# Main_cicuit.net
KiCad netlist of a schematic drawn in Altium Designer
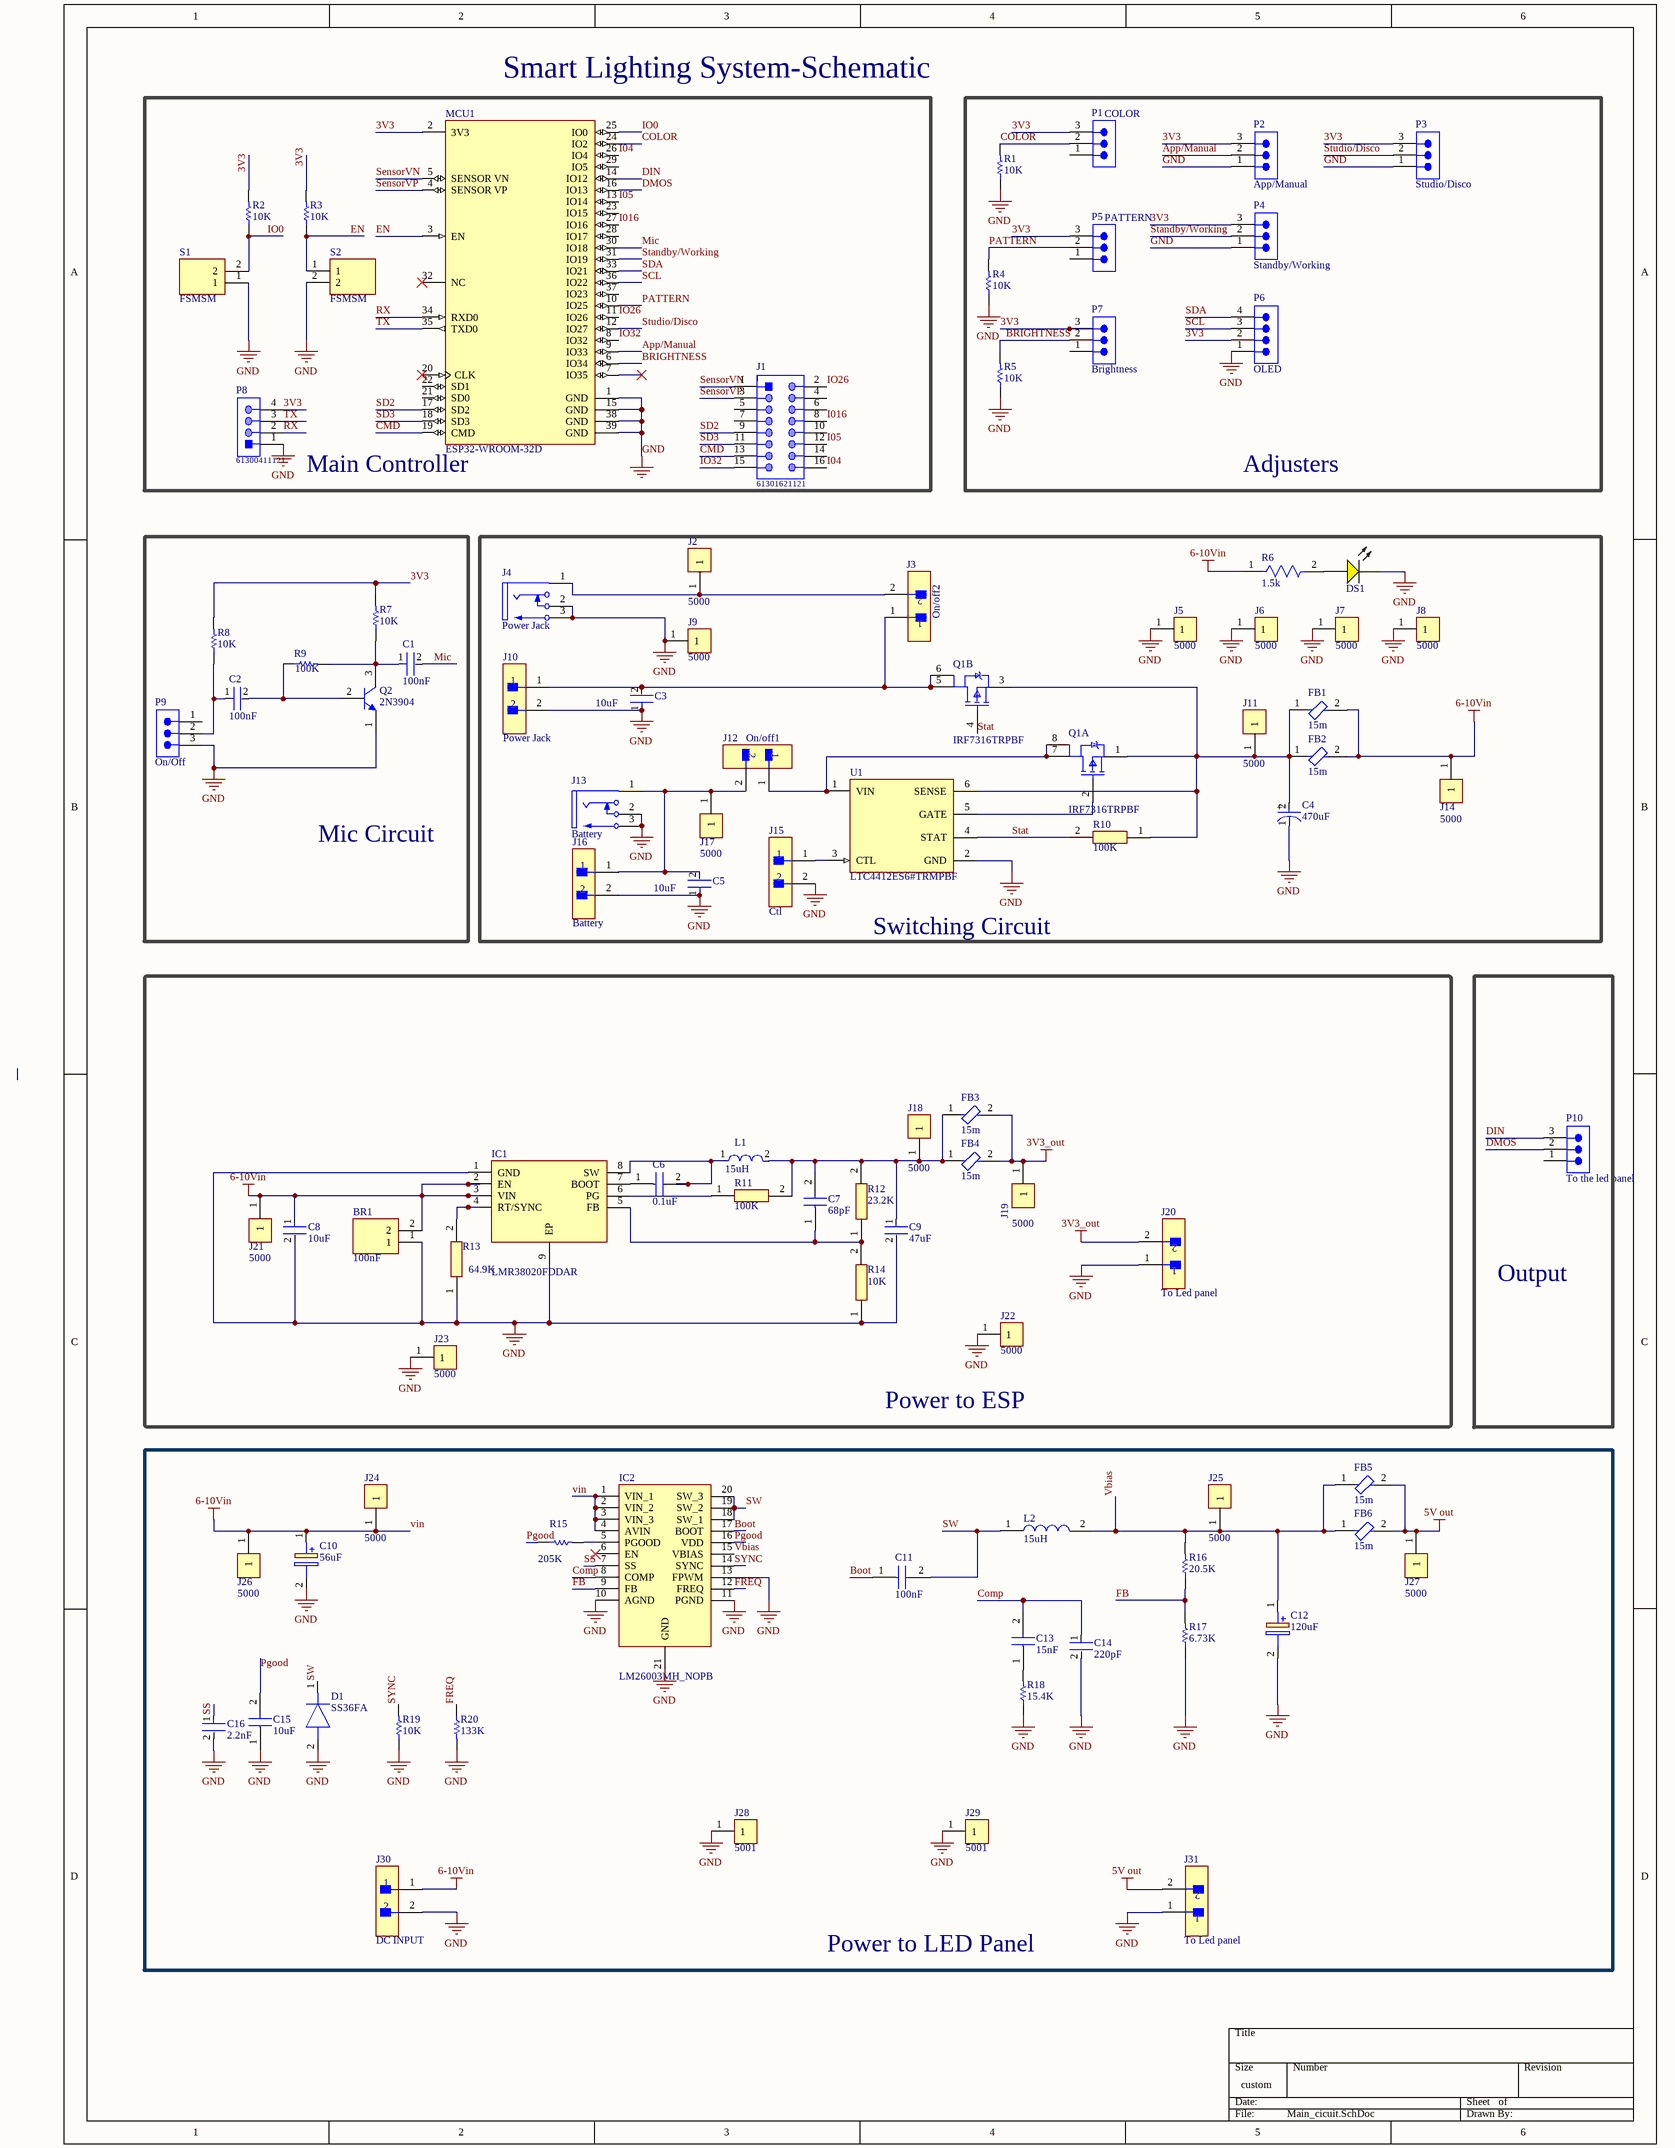
[diagram p0: Main_cicuit.SchDoc]

(export (version "E")
  (design (tool "Eeschema 10.0.6"))
  (components
    (comp (ref "BR1")
      (value "100nF")
      (footprint "SamacSys:CAPC3216X140N")
      (description "Bridge Rectifier")
      (fields
        (field (name "MANUFACTURER_PART_NUMBER") "C1206C104M4RECTU")
        (field (name "MOUSER PART NUMBER") "80-C1206C104M4RECTU")
      )
      (libsource (lib "*") (part "C1206C104M4RECTU"))
    )
    (comp (ref "C1")
      (value "100nF")
      (footprint "FP-CL31-IPC_C")
      (description "Cap Ceramic 100nF 100V X7R ±10% SMD 1206 +125°C Embossed T/R")
      (fields (field (name "VOLTAGE") "100V") (field (name "TOLERANCE") "10%"))
      (libsource (lib "Altium Content Vault") (part "b4654b650e69147ec39a6b967a45e02"))
    )
    (comp (ref "C2")
      (value "100nF")
      (footprint "FP-CL31-IPC_C")
      (description "Cap Ceramic 100nF 100V X7R ±10% SMD 1206 +125°C Embossed T/R")
      (fields (field (name "VOLTAGE") "100V") (field (name "TOLERANCE") "10%"))
      (libsource (lib "Altium Content Vault") (part "b4654b650e69147ec39a6b967a45e02"))
    )
    (comp (ref "C3")
      (value "10uF")
      (footprint "FP-CL21B106KOQNNNG-MFG")
      (description "CAP CER 10UF 16V X7R 0805")
      (fields (field (name "TOLERANCE") "10%") (field (name "MANUFACTURER PART NUMBER") "CL21B106KOQNNNG"))
      (libsource (lib "Altium Content Vault") (part "b4654b650e69147ec39a6b967a45e02"))
    )
    (comp (ref "C4")
      (value "470uF")
      (footprint "FP-FTF-MFG")
      (description "CAP ALUM 470UF 20% 25V SMD")
      (fields (field (name "VOLTAGE") "25V") (field (name "TOLERANCE") "20%"))
      (libsource (lib "Altium Content Vault") (part "a00bbbee19879c290e62620ae7e47b1"))
    )
    (comp (ref "C5")
      (value "10uF")
      (footprint "FP-CL21B106KOQNNNG-MFG")
      (description "CAP CER 10UF 16V X7R 0805")
      (fields (field (name "TOLERANCE") "10%") (field (name "MANUFACTURER PART NUMBER") "CL21B106KOQNNNG"))
      (libsource (lib "Altium Content Vault") (part "b4654b650e69147ec39a6b967a45e02"))
    )
    (comp (ref "C6")
      (value "0.1uF")
      (footprint "SamacSys:CAPC3216X200N")
      (description "Capacitor")
      (fields
        (field (name "MANUFACTURER_PART_NUMBER") "GCJ31CR72E104KXJ3L")
        (field (name "MOUSER PART NUMBER") "81-GCJ31CR72E104KX3L")
      )
      (libsource (lib "*") (part "GCJ31CR72E104KXJ3L"))
    )
    (comp (ref "C7")
      (value "68pF")
      (footprint "SamacSys:CAPC3216X90N")
      (description "Capacitor")
      (fields (field (name "MANUFACTURER_PART_NUMBER") "885012008022"))
      (libsource (lib "*") (part "885012008022"))
    )
    (comp (ref "C8")
      (value "10uF")
      (footprint "FP-GRM31C-0_2-e0_3_0_8-MFG")
      (description "Chip Multilayer Ceramic Capacitors for General Purpose, 1206, 10uF, X7R, 15%, 10%, 25V")
      (fields (field (name "TOLERANCE") "10%") (field (name "VOLTAGE") "25V"))
      (libsource (lib "Altium Content Vault") (part "02cd4be3c70576c341d710602a673aa"))
    )
    (comp (ref "C9")
      (value "47uF")
      (footprint "FP-1206-L_3_2_0_3-W_1_6_0-MFG")
      (description "None")
      (fields (field (name "TOLERANCE") "20%"))
      (libsource (lib "Altium Content Vault") (part "11868f565c42a9108669ba33697ecf6"))
    )
    (comp (ref "C10")
      (value "56uF")
      (footprint "SamacSys:EEHZA1E101XP")
      (description "Capacitor Polarised")
      (fields
        (field (name "MANUFACTURER_PART_NUMBER") "EEH-ZC1E560P")
        (field (name "MOUSER PART NUMBER") "667-EEH-ZC1E560P")
      )
      (libsource (lib "*") (part "EEH-ZC1E560P"))
    )
    (comp (ref "C11")
      (value "100nF")
      (footprint "SamacSys:CAPC2013X94N")
      (description "Capacitor")
      (fields
        (field (name "MANUFACTURER_PART_NUMBER") "08053C104JAZ2A")
        (field (name "MOUSER PART NUMBER") "581-08053C104JAZ2A")
      )
      (libsource (lib "*") (part "08053C104JAZ2A"))
    )
    (comp (ref "C12")
      (value "120uF")
      (footprint "SamacSys:10SVPC120M")
      (description "Capacitor Polarised")
      (fields
        (field (name "MANUFACTURER_PART_NUMBER") "10SVPC120M")
        (field (name "MOUSER PART NUMBER") "667-10SVPC120M")
      )
      (libsource (lib "*") (part "10SVPC120M"))
    )
    (comp (ref "C13")
      (value "15nF")
      (footprint "SamacSys:C2012_Commercial")
      (description "Capacitor")
      (fields
        (field (name "MANUFACTURER_PART_NUMBER") "C2012C0G1H153J085AA")
        (field (name "MOUSER PART NUMBER") "810-C2012C0G1H153J")
      )
      (libsource (lib "*") (part "C2012C0G1H153J085AA"))
    )
    (comp (ref "C14")
      (value "220pF")
      (footprint "FP-CL21-IPC_B")
      (description "CL21 Series 0805 220pF 50V ±5% Tolerance C0G Multilayer Ceramic Chip Capacitor")
      (fields (field (name "TOLERANCE") "5%") (field (name "VOLTAGE") "50V"))
      (libsource (lib "Altium Content Vault") (part "b4654b650e69147ec39a6b967a45e02"))
    )
    (comp (ref "C15")
      (value "10uF")
      (footprint "SamacSys:CAPC3216X170N")
      (description "Capacitor")
      (fields
        (field (name "MANUFACTURER_PART_NUMBER") "VJ1206G106KXYTW1BC")
        (field (name "MOUSER PART NUMBER") "77-VJ1206G106KXYTBC")
      )
      (libsource (lib "*") (part "VJ1206G106KXYTW1BC"))
    )
    (comp (ref "C16")
      (value "2.2nF")
      (footprint "FP-CL21-IPC_C")
      (description "CL21 Series 0805 2.2nF 50V ±5% Tolerance C0G Multilayer Ceramic Chip Capacitor")
      (fields (field (name "TOLERANCE") "5%") (field (name "VOLTAGE") "50V"))
      (libsource (lib "Altium Content Vault") (part "b4654b650e69147ec39a6b967a45e02"))
    )
    (comp (ref "D1")
      (value "SS36FA")
      (footprint "SamacSys:SODFL3618X143N")
      (description "Diode")
      (fields (field (name "MOUSER PART NUMBER") "512-SS36FA"))
      (libsource (lib "*") (part "SS36FA"))
    )
    (comp (ref "DS1")
      (value "SML-LX1206YC-TR")
      (footprint "LUMX-SML-LX1206YC-TR_V")
      (description "Yellow LED, Water Clear Len, 585 nm, 2.1 V, -40 to 85 degC, 2-Pin SMD, RoHS, Tape and Reel")
      (fields (field (name "MANUFACTURER") "Lumex"))
      (libsource (lib "Altium Content Vault") (part "LED-YELLOW-AK-2"))
    )
    (comp (ref "FB1")
      (value "15m")
      (footprint "FP-BLM21-0_2-t0_85-e0_5-d-IPC_B")
      (description "Chip Ferrite Bead, 0805, 30Ω @ 100MHz, 0.014Ω, , 4A")
      (fields (field (name "TOLERANCE") "25%"))
      (libsource (lib "Altium Content Vault") (part "5f30dd21d616792df468990f7003faa"))
    )
    (comp (ref "FB2")
      (value "15m")
      (footprint "FP-BLM21-0_2-t0_85-e0_5-d-IPC_B")
      (description "Chip Ferrite Bead, 0805, 30Ω @ 100MHz, 0.014Ω, , 4A")
      (fields (field (name "TOLERANCE") "25%"))
      (libsource (lib "Altium Content Vault") (part "5f30dd21d616792df468990f7003faa"))
    )
    (comp (ref "FB3")
      (value "15m")
      (footprint "FP-BLM21-0_2-t0_85-e0_5-d-IPC_B")
      (description "Chip Ferrite Bead, 0805, 30Ω @ 100MHz, 0.014Ω, , 4A")
      (fields (field (name "TOLERANCE") "25%"))
      (libsource (lib "Altium Content Vault") (part "5f30dd21d616792df468990f7003faa"))
    )
    (comp (ref "FB4")
      (value "15m")
      (footprint "FP-BLM21-0_2-t0_85-e0_5-d-IPC_B")
      (description "Chip Ferrite Bead, 0805, 30Ω @ 100MHz, 0.014Ω, , 4A")
      (fields (field (name "TOLERANCE") "25%"))
      (libsource (lib "Altium Content Vault") (part "5f30dd21d616792df468990f7003faa"))
    )
    (comp (ref "FB5")
      (value "15m")
      (footprint "FP-BLM21-0_2-t0_85-e0_5-d-IPC_B")
      (description "Chip Ferrite Bead, 0805, 30Ω @ 100MHz, 0.014Ω, , 4A")
      (fields (field (name "TOLERANCE") "25%"))
      (libsource (lib "Altium Content Vault") (part "5f30dd21d616792df468990f7003faa"))
    )
    (comp (ref "FB6")
      (value "15m")
      (footprint "FP-BLM21-0_2-t0_85-e0_5-d-IPC_B")
      (description "Chip Ferrite Bead, 0805, 30Ω @ 100MHz, 0.014Ω, , 4A")
      (fields (field (name "TOLERANCE") "25%"))
      (libsource (lib "Altium Content Vault") (part "5f30dd21d616792df468990f7003faa"))
    )
    (comp (ref "IC1")
      (value "LMR38020FDDAR")
      (footprint "SamacSys:SOIC127P600X170-9N")
      (description "Integrated Circuit")
      (fields (field (name "MOUSER PART NUMBER") "595-LMR38020FDDAR"))
      (libsource (lib "*") (part "LMR38020FDDAR"))
    )
    (comp (ref "IC2")
      (value "LM26003MH_NOPB")
      (footprint "SamacSys:SOP65P640X110-21N")
      (description "Integrated Circuit")
      (fields
        (field (name "MANUFACTURER_PART_NUMBER") "LM26003MH/NOPB")
        (field (name "MOUSER PART NUMBER") "926-LM26003MH/NOPB")
      )
      (libsource (lib "*") (part "LM26003MH_NOPB"))
    )
    (comp (ref "J1")
      (value "61301621121")
      (footprint "61301621121")
      (description "THT Vertical Pin Header WR-PHD, Pitch 2.54 mm, Dual Row, 16 pins")
      (fields (field (name "MANUFACTURER") "Wurth Elektronik") (field (name "PUBLISHER") "WurthElektronik"))
      (libsource (lib "Altium Content Vault") (part "WE-CN-2P-M-R16"))
    )
    (comp (ref "J2")
      (value "5000")
      (footprint "FP-5000-MFG")
      (description "PC TEST POINT MINIATURE RED")
      (libsource (lib "") (part "1e4615820a309e3ce90f9e6d957b7fa_1"))
    )
    (comp (ref "J3")
      (value "On/off2")
      (footprint "FP-61900211121-MFG")
      (description "CONN HEADER VERT 2POS 2.54MM")
      (libsource (lib "") (part "3bc925449376181038e59eaffc5286c_1"))
    )
    (comp (ref "J4")
      (value "Power Jack")
      (footprint "SWITCH-RAPC712X-3_V")
      (description "Power Jack, 5 A, 3-Pin THD, RoHS, Bulk")
      (fields (field (name "MANUFACTURER") "Switchcraft"))
      (libsource (lib "Altium Content Vault") (part "SWITCH-RAPC712X-3"))
    )
    (comp (ref "J5")
      (value "5000")
      (footprint "FP-5000-MFG")
      (description "PC TEST POINT MINIATURE RED")
      (libsource (lib "Altium Content Vault") (part "1e4615820a309e3ce90f9e6d957b7fa"))
    )
    (comp (ref "J6")
      (value "5000")
      (footprint "FP-5000-MFG")
      (description "PC TEST POINT MINIATURE RED")
      (libsource (lib "Altium Content Vault") (part "1e4615820a309e3ce90f9e6d957b7fa"))
    )
    (comp (ref "J7")
      (value "5000")
      (footprint "FP-5000-MFG")
      (description "PC TEST POINT MINIATURE RED")
      (libsource (lib "Altium Content Vault") (part "1e4615820a309e3ce90f9e6d957b7fa"))
    )
    (comp (ref "J8")
      (value "5000")
      (footprint "FP-5000-MFG")
      (description "PC TEST POINT MINIATURE RED")
      (libsource (lib "Altium Content Vault") (part "1e4615820a309e3ce90f9e6d957b7fa"))
    )
    (comp (ref "J9")
      (value "5000")
      (footprint "FP-5000-MFG")
      (description "PC TEST POINT MINIATURE RED")
      (libsource (lib "Altium Content Vault") (part "1e4615820a309e3ce90f9e6d957b7fa"))
    )
    (comp (ref "J10")
      (value "Power Jack")
      (footprint "FP-61900211121-MFG")
      (description "CONN HEADER VERT 2POS 2.54MM")
      (libsource (lib "Altium Content Vault") (part "3bc925449376181038e59eaffc5286c"))
    )
    (comp (ref "J11")
      (value "5000")
      (footprint "FP-5000-MFG")
      (description "PC TEST POINT MINIATURE RED")
      (libsource (lib "") (part "1e4615820a309e3ce90f9e6d957b7fa_1"))
    )
    (comp (ref "J12")
      (value "On/off1")
      (footprint "FP-61900211121-MFG")
      (description "CONN HEADER VERT 2POS 2.54MM")
      (libsource (lib "") (part "3bc925449376181038e59eaffc5286c_2"))
    )
    (comp (ref "J13")
      (value "Battery")
      (footprint "SWITCH-RAPC712X-3_V")
      (description "Power Jack, 5 A, 3-Pin THD, RoHS, Bulk")
      (fields (field (name "MANUFACTURER") "Switchcraft"))
      (libsource (lib "Altium Content Vault") (part "SWITCH-RAPC712X-3"))
    )
    (comp (ref "J14")
      (value "5000")
      (footprint "FP-5000-MFG")
      (description "PC TEST POINT MINIATURE RED")
      (libsource (lib "") (part "1e4615820a309e3ce90f9e6d957b7fa_2"))
    )
    (comp (ref "J15")
      (value "Ctl")
      (footprint "FP-61900211121-MFG")
      (description "CONN HEADER VERT 2POS 2.54MM")
      (libsource (lib "Altium Content Vault") (part "3bc925449376181038e59eaffc5286c"))
    )
    (comp (ref "J16")
      (value "Battery")
      (footprint "FP-61900211121-MFG")
      (description "CONN HEADER VERT 2POS 2.54MM")
      (libsource (lib "Altium Content Vault") (part "3bc925449376181038e59eaffc5286c"))
    )
    (comp (ref "J17")
      (value "5000")
      (footprint "FP-5000-MFG")
      (description "PC TEST POINT MINIATURE RED")
      (libsource (lib "") (part "1e4615820a309e3ce90f9e6d957b7fa_2"))
    )
    (comp (ref "J18")
      (value "5000")
      (footprint "FP-5000-MFG")
      (description "PC TEST POINT MINIATURE RED")
      (libsource (lib "") (part "1e4615820a309e3ce90f9e6d957b7fa_1"))
    )
    (comp (ref "J19")
      (value "5000")
      (footprint "FP-5000-MFG")
      (description "PC TEST POINT MINIATURE RED")
      (libsource (lib "") (part "1e4615820a309e3ce90f9e6d957b7fa_2"))
    )
    (comp (ref "J20")
      (value "To Led panel")
      (footprint "FP-61900211121-MFG")
      (description "CONN HEADER VERT 2POS 2.54MM")
      (libsource (lib "") (part "3bc925449376181038e59eaffc5286c_1"))
    )
    (comp (ref "J21")
      (value "5000")
      (footprint "FP-5000-MFG")
      (description "PC TEST POINT MINIATURE RED")
      (libsource (lib "") (part "1e4615820a309e3ce90f9e6d957b7fa_2"))
    )
    (comp (ref "J22")
      (value "5000")
      (footprint "FP-5000-MFG")
      (description "PC TEST POINT MINIATURE RED")
      (libsource (lib "Altium Content Vault") (part "1e4615820a309e3ce90f9e6d957b7fa"))
    )
    (comp (ref "J23")
      (value "5000")
      (footprint "FP-5000-MFG")
      (description "PC TEST POINT MINIATURE RED")
      (libsource (lib "Altium Content Vault") (part "1e4615820a309e3ce90f9e6d957b7fa"))
    )
    (comp (ref "J24")
      (value "5000")
      (footprint "FP-5000-MFG")
      (description "PC TEST POINT MINIATURE RED")
      (libsource (lib "") (part "1e4615820a309e3ce90f9e6d957b7fa_1"))
    )
    (comp (ref "J25")
      (value "5000")
      (footprint "FP-5000-MFG")
      (description "PC TEST POINT MINIATURE RED")
      (libsource (lib "") (part "1e4615820a309e3ce90f9e6d957b7fa_1"))
    )
    (comp (ref "J26")
      (value "5000")
      (footprint "FP-5000-MFG")
      (description "PC TEST POINT MINIATURE RED")
      (libsource (lib "") (part "1e4615820a309e3ce90f9e6d957b7fa_2"))
    )
    (comp (ref "J27")
      (value "5000")
      (footprint "FP-5000-MFG")
      (description "PC TEST POINT MINIATURE RED")
      (libsource (lib "") (part "1e4615820a309e3ce90f9e6d957b7fa_2"))
    )
    (comp (ref "J28")
      (value "5001")
      (footprint "FP-5001-MFG")
      (description "PC TEST POINT MINIATURE BLACK")
      (libsource (lib "Altium Content Vault") (part "1e4615820a309e3ce90f9e6d957b7fa"))
    )
    (comp (ref "J29")
      (value "5001")
      (footprint "FP-5001-MFG")
      (description "PC TEST POINT MINIATURE BLACK")
      (libsource (lib "Altium Content Vault") (part "1e4615820a309e3ce90f9e6d957b7fa"))
    )
    (comp (ref "J30")
      (value "DC INPUT")
      (footprint "FP-61900211121-MFG")
      (description "CONN HEADER VERT 2POS 2.54MM")
      (libsource (lib "Altium Content Vault") (part "3bc925449376181038e59eaffc5286c"))
    )
    (comp (ref "J31")
      (value "To Led panel")
      (footprint "FP-61900211121-MFG")
      (description "CONN HEADER VERT 2POS 2.54MM")
      (libsource (lib "") (part "3bc925449376181038e59eaffc5286c_1"))
    )
    (comp (ref "L1")
      (value "15uH")
      (footprint "FP-SRR1260-MFG")
      (description "FIXED IND 15UH 5A 27 MOHM SMD")
      (fields (field (name "TOLERANCE") "20%"))
      (libsource (lib "Altium Content Vault") (part "725321dda6339637d4d059423bc1c3c"))
    )
    (comp (ref "L2")
      (value "15uH")
      (footprint "SamacSys:INDPM7366X300N")
      (description "Inductor")
      (fields
        (field (name "MANUFACTURER_PART_NUMBER") "SRP7028A-150M")
        (field (name "MOUSER PART NUMBER") "652-SRP7028A-150M")
      )
      (libsource (lib "*") (part "SRP7028A-150M"))
    )
    (comp (ref "MCU1")
      (value "ESP32-WROOM-32D")
      (footprint "FP-ESP32-WROOM-32D-MFG")
      (description "WIFI MODULE 32MBITS SPI FLASH")
      (fields
        (field (name "OCTOPART") "https://octopart.com/esp32-wroom-32d-espressif+systems-91040050")
        (field (name "MANUFACTURER") "Espressif Systems")
      )
      (libsource (lib "Altium Content Vault") (part "a031a76f8c27026a7a7f4657ff233a3"))
    )
    (comp (ref "P1")
      (value "COLOR")
      (footprint "SMTC-TSW-103-07-X-S")
      (description "0.025\" SQ Post Header, Through-hole, Vertical, -55 to 125 degC, 2.54 mm Pitch, 3-Pin, Male, RoHS")
      (fields (field (name "MANUFACTURER") "Samtec") (field (name "PARTNUMBER") "TSW-103-07-F-S"))
      (libsource (lib "Altium Content Vault") (part "SMTC-TSW-103-X-X-S-X"))
    )
    (comp (ref "P2")
      (value "App/Manual")
      (footprint "SMTC-TSW-103-07-X-S")
      (description "0.025\" SQ Post Header, Through-hole, Vertical, -55 to 125 degC, 2.54 mm Pitch, 3-Pin, Male, RoHS")
      (fields (field (name "MANUFACTURER") "Samtec") (field (name "PARTNUMBER") "TSW-103-07-F-S"))
      (libsource (lib "Altium Content Vault") (part "SMTC-TSW-103-X-X-S-X"))
    )
    (comp (ref "P3")
      (value "Studio/Disco")
      (footprint "SMTC-TSW-103-07-X-S")
      (description "0.025\" SQ Post Header, Through-hole, Vertical, -55 to 125 degC, 2.54 mm Pitch, 3-Pin, Male, RoHS")
      (fields (field (name "MANUFACTURER") "Samtec") (field (name "PARTNUMBER") "TSW-103-07-F-S"))
      (libsource (lib "Altium Content Vault") (part "SMTC-TSW-103-X-X-S-X"))
    )
    (comp (ref "P4")
      (value "Standby/Working")
      (footprint "SMTC-TSW-103-07-X-S")
      (description "0.025\" SQ Post Header, Through-hole, Vertical, -55 to 125 degC, 2.54 mm Pitch, 3-Pin, Male, RoHS")
      (fields (field (name "MANUFACTURER") "Samtec") (field (name "PARTNUMBER") "TSW-103-07-F-S"))
      (libsource (lib "Altium Content Vault") (part "SMTC-TSW-103-X-X-S-X"))
    )
    (comp (ref "P5")
      (value "PATTERN")
      (footprint "SMTC-TSW-103-07-X-S")
      (description "0.025\" SQ Post Header, Through-hole, Vertical, -55 to 125 degC, 2.54 mm Pitch, 3-Pin, Male, RoHS")
      (fields (field (name "MANUFACTURER") "Samtec") (field (name "PARTNUMBER") "TSW-103-07-F-S"))
      (libsource (lib "Altium Content Vault") (part "SMTC-TSW-103-X-X-S-X"))
    )
    (comp (ref "P6")
      (value "OLED")
      (footprint "SMTC-TSW-104-08-X-S")
      (description "0.025\" SQ Post Header, Through-hole, Vertical, -55 to 125 degC, 2.54 mm Pitch, 4-Pin, Male, RoHS")
      (fields (field (name "MANUFACTURER") "Samtec") (field (name "PARTNUMBER") "TSW-104-08-G-S"))
      (libsource (lib "Altium Content Vault") (part "SMTC-TSW-104-08-X-S"))
    )
    (comp (ref "P7")
      (value "Brightness")
      (footprint "SMTC-TSW-103-07-X-S")
      (description "0.025\" SQ Post Header, Through-hole, Vertical, -55 to 125 degC, 2.54 mm Pitch, 3-Pin, Male, RoHS")
      (fields (field (name "MANUFACTURER") "Samtec") (field (name "PARTNUMBER") "TSW-103-07-F-S"))
      (libsource (lib "Altium Content Vault") (part "SMTC-TSW-103-X-X-S-X"))
    )
    (comp (ref "P8")
      (value "61300411121")
      (footprint "61300411121")
      (description "THT Vertical Pin Header WR-PHD, Pitch 2.54 mm, Single Row, 4 pins")
      (fields (field (name "MANUFACTURER") "Wurth Elektronik") (field (name "PUBLISHER") "WurthElektronik"))
      (libsource (lib "Altium Content Vault") (part "WE-CN-1P-M-R4"))
    )
    (comp (ref "P9")
      (value "On/Off")
      (footprint "SMTC-TSW-103-07-X-S")
      (description "0.025\" SQ Post Header, Through-hole, Vertical, -55 to 125 degC, 2.54 mm Pitch, 3-Pin, Male, RoHS")
      (fields (field (name "MANUFACTURER") "Samtec") (field (name "PARTNUMBER") "TSW-103-07-F-S"))
      (libsource (lib "Altium Content Vault") (part "SMTC-TSW-103-X-X-S-X"))
    )
    (comp (ref "P10")
      (value "To the led panel")
      (footprint "SMTC-TSW-103-07-X-S")
      (description "0.025\" SQ Post Header, Through-hole, Vertical, -55 to 125 degC, 2.54 mm Pitch, 3-Pin, Male, RoHS")
      (fields (field (name "MANUFACTURER") "Samtec") (field (name "PARTNUMBER") "TSW-103-07-F-S"))
      (libsource (lib "Altium Content Vault") (part "SMTC-TSW-103-X-X-S-X"))
    )
    (comp (ref "Q1")
      (value "IRF7316TRPBF")
      (footprint "FP-PG-DSO-8-IPC_B")
      (description "MOSFET 2P-CH 30V 4.9A 8-SOIC")
      (libsource (lib "Altium Content Vault") (part "492061ec32f27a5842dd38c1d0dc3fb"))
    )
    (comp (ref "Q2")
      (value "2N3904")
      (footprint "ONSC-TO-92-3-29-11")
      (description "General Purpose Transistor, NPN Silicon, 200 mA, 60 V, -55 to 150 degC, 3-Pin TO-92, RoHS, Bulk")
      (fields (field (name "MANUFACTURER") "ONSemiconductor"))
      (libsource (lib "Altium Content Vault") (part "BJT-NPN-EBC-3"))
    )
    (comp (ref "R1")
      (value "10K")
      (footprint "RESC3116X65X40ML10T20")
      (description "Chip Resistor, 10 KOhm, +/- 1%, 0.25 W, -55 to 155 degC, 1206 (3216 Metric), RoHS, Tape and Reel")
      (fields (field (name "TOLERANCE") "1%") (field (name "MANUFACTURER") "Yageo"))
      (libsource (lib "Altium Content Vault") (part "RES-2"))
    )
    (comp (ref "R2")
      (value "10K")
      (footprint "RESC3116X65X40ML10T20")
      (description "Chip Resistor, 10 KOhm, +/- 1%, 0.25 W, -55 to 155 degC, 1206 (3216 Metric), RoHS, Tape and Reel")
      (fields (field (name "TOLERANCE") "1%") (field (name "MANUFACTURER") "Yageo"))
      (libsource (lib "Altium Content Vault") (part "RES-2"))
    )
    (comp (ref "R3")
      (value "10K")
      (footprint "RESC3116X65X40ML10T20")
      (description "Chip Resistor, 10 KOhm, +/- 1%, 0.25 W, -55 to 155 degC, 1206 (3216 Metric), RoHS, Tape and Reel")
      (fields (field (name "TOLERANCE") "1%") (field (name "MANUFACTURER") "Yageo"))
      (libsource (lib "Altium Content Vault") (part "RES-2"))
    )
    (comp (ref "R4")
      (value "10K")
      (footprint "RESC3116X65X40ML10T20")
      (description "Chip Resistor, 10 KOhm, +/- 1%, 0.25 W, -55 to 155 degC, 1206 (3216 Metric), RoHS, Tape and Reel")
      (fields (field (name "TOLERANCE") "1%") (field (name "MANUFACTURER") "Yageo"))
      (libsource (lib "Altium Content Vault") (part "RES-2"))
    )
    (comp (ref "R5")
      (value "10K")
      (footprint "RESC3116X65X40ML10T20")
      (description "Chip Resistor, 10 KOhm, +/- 1%, 0.25 W, -55 to 155 degC, 1206 (3216 Metric), RoHS, Tape and Reel")
      (fields (field (name "TOLERANCE") "1%") (field (name "MANUFACTURER") "Yageo"))
      (libsource (lib "Altium Content Vault") (part "RES-2"))
    )
    (comp (ref "R6")
      (value "1.5k")
      (footprint "FP-CRCW1206-e3-IPC_C")
      (description "RES Thick Film, 1.5kΩ, 1%, 0.25W, 100ppm/°C, 1206")
      (fields (field (name "TOLERANCE") "1%"))
      (libsource (lib "Altium Content Vault") (part "1029c3af85768c4190bb7ad29bc67b5"))
    )
    (comp (ref "R7")
      (value "10K")
      (footprint "RESC3116X65X40ML10T20")
      (description "Chip Resistor, 10 KOhm, +/- 1%, 0.25 W, -55 to 155 degC, 1206 (3216 Metric), RoHS, Tape and Reel")
      (fields (field (name "TOLERANCE") "1%") (field (name "MANUFACTURER") "Yageo"))
      (libsource (lib "Altium Content Vault") (part "RES-2"))
    )
    (comp (ref "R8")
      (value "10K")
      (footprint "RESC3116X65X40ML10T20")
      (description "Chip Resistor, 10 KOhm, +/- 1%, 0.25 W, -55 to 155 degC, 1206 (3216 Metric), RoHS, Tape and Reel")
      (fields (field (name "TOLERANCE") "1%") (field (name "MANUFACTURER") "Yageo"))
      (libsource (lib "Altium Content Vault") (part "RES-2"))
    )
    (comp (ref "R9")
      (value "100K")
      (footprint "RESC3116X65X40ML10T20")
      (description "Chip Resistor, 100 KOhm, +/- 1%, 0.25 W, -55 to 155 degC, 1206 (3216 Metric), RoHS, Tape and Reel")
      (fields (field (name "TOLERANCE") "1%") (field (name "MANUFACTURER") "Yageo"))
      (libsource (lib "Altium Content Vault") (part "RES-2"))
    )
    (comp (ref "R10")
      (value "100K")
      (footprint "SamacSys:RESC3116X65N")
      (description "Resistor")
      (fields
        (field (name "MANUFACTURER_PART_NUMBER") "CRM1206QFX-1003ELF")
        (field (name "MOUSER PART NUMBER") "652-CRM1206QFX-1003E")
      )
      (libsource (lib "*") (part "CRM1206QFX-1003ELF"))
    )
    (comp (ref "R11")
      (value "100K")
      (footprint "SamacSys:RESC3116X65N")
      (description "Resistor")
      (fields
        (field (name "MANUFACTURER_PART_NUMBER") "CRM1206QFX-1003ELF")
        (field (name "MOUSER PART NUMBER") "652-CRM1206QFX-1003E")
      )
      (libsource (lib "") (part "CRM1206QFX-1003ELF_1"))
    )
    (comp (ref "R12")
      (value "23.2K")
      (footprint "SamacSys:ERJ8ENF1000V")
      (description "Resistor")
      (fields
        (field (name "MANUFACTURER_PART_NUMBER") "ERJ-8ENF2322V")
        (field (name "MOUSER PART NUMBER") "667-ERJ-8ENF2322V")
      )
      (libsource (lib "*") (part "ERJ-8ENF2322V"))
    )
    (comp (ref "R13")
      (value "64.9K")
      (footprint "SamacSys:ERJ8ENF1000V")
      (description "Resistor")
      (fields
        (field (name "MANUFACTURER_PART_NUMBER") "ERJ-8ENF6492V")
        (field (name "MOUSER PART NUMBER") "667-ERJ-8ENF6492V")
      )
      (libsource (lib "*") (part "ERJ-8ENF6492V"))
    )
    (comp (ref "R14")
      (value "10K")
      (footprint "SamacSys:ERJ8ENF1000V")
      (description "Resistor")
      (fields
        (field (name "MANUFACTURER_PART_NUMBER") "ERJ-8ENF1002V")
        (field (name "MOUSER PART NUMBER") "667-ERJ-8ENF1002V")
      )
      (libsource (lib "*") (part "ERJ-8ENF1002V"))
    )
    (comp (ref "R15")
      (value "205K")
      (footprint "RESC3216X60X45NL10T20")
      (fields (field (name "MANUFACTURER") "Vishay Dale") (field (name "PART NUMBER") "CRCW1206205KFKEA"))
      (libsource (lib "Altium Content Vault") (part "RES"))
    )
    (comp (ref "R16")
      (value "20.5K")
      (footprint "RESC2013X70X40NL20T20")
      (fields (field (name "MANUFACTURER") "Panasonic") (field (name "PART NUMBER") "ERJ-6ENF2052V"))
      (libsource (lib "Altium Content Vault") (part "RES"))
    )
    (comp (ref "R17")
      (value "6.73K")
      (footprint "RESC2013X60X35NL10T20")
      (description "Chip Resistor, 10 KOhm, +/- 1%, 0.125 W, -55 to 155 degC, 0805 (2012 Metric), RoHS, Tape and Reel")
      (fields (field (name "MANUFACTURER") "Yageo"))
      (libsource (lib "Altium Content Vault") (part "RES-2"))
    )
    (comp (ref "R18")
      (value "15.4K")
      (footprint "RESC3216X70X50LL05T20")
      (fields (field (name "PART NUMBER") "ERJ-8ENF1542V") (field (name "MANUFACTURER") "Panasonic"))
      (libsource (lib "Altium Content Vault") (part "RES"))
    )
    (comp (ref "R19")
      (value "10K")
      (footprint "RESC3116X65X40ML10T20")
      (description "Chip Resistor, 10 KOhm, +/- 1%, 0.25 W, -55 to 155 degC, 1206 (3216 Metric), RoHS, Tape and Reel")
      (fields (field (name "TOLERANCE") "1%") (field (name "MANUFACTURER") "Yageo"))
      (libsource (lib "Altium Content Vault") (part "RES-2"))
    )
    (comp (ref "R20")
      (value "133K")
      (footprint "RESC3216X70X50LL20T25")
      (fields (field (name "MANUFACTURER") "Panasonic") (field (name "PART NUMBER") "ERA-8AEB1333V"))
      (libsource (lib "Altium Content Vault") (part "RES"))
    )
    (comp (ref "S1")
      (value "FSMSM")
      (footprint "SamacSys:FSMSM")
      (description "Switch")
      (fields (field (name "MOUSER PART NUMBER") "506-FSMSM"))
      (libsource (lib "") (part "FSMSM_1"))
    )
    (comp (ref "S2")
      (value "FSMSM")
      (footprint "SamacSys:FSMSM")
      (description "Switch")
      (fields (field (name "MOUSER PART NUMBER") "506-FSMSM"))
      (libsource (lib "*") (part "FSMSM"))
    )
    (comp (ref "U1")
      (value "LTC4412ES6#TRMPBF")
      (footprint "FP-S6-6-05-08-1636-IPC_C")
      (description "IC OR CTRLR SRC SELECT TSOT23-6")
      (libsource (lib "Altium Content Vault") (part "07cb0f4431a3a7488227ca1baae77bb"))
    )
  )
  (nets
    (net (code "1") (name "/3V3") (class "Default")
      (node (ref "MCU1") (pin "2") (pinfunction "3V3_2") (pintype "power_in"))
      (node (ref "P1") (pin "3") (pinfunction "3_3") (pintype "passive"))
      (node (ref "P2") (pin "3") (pinfunction "3_3") (pintype "passive"))
      (node (ref "P3") (pin "3") (pinfunction "3_3") (pintype "passive"))
      (node (ref "P4") (pin "3") (pinfunction "3_3") (pintype "passive"))
      (node (ref "P5") (pin "3") (pinfunction "3_3") (pintype "passive"))
      (node (ref "P6") (pin "2") (pinfunction "2_2") (pintype "passive"))
      (node (ref "P7") (pin "3") (pinfunction "3_3") (pintype "passive"))
      (node (ref "P8") (pin "4") (pinfunction "4_4") (pintype "passive"))
      (node (ref "R2") (pin "2") (pinfunction "2_2") (pintype "passive"))
      (node (ref "R3") (pin "2") (pinfunction "2_2") (pintype "passive"))
      (node (ref "R7") (pin "2") (pinfunction "2_2") (pintype "passive"))
      (node (ref "R8") (pin "2") (pinfunction "2_2") (pintype "passive"))
    )
    (net (code "2") (name "/App{slash}Manual") (class "Default")
      (node (ref "MCU1") (pin "9") (pinfunction "IO33_9") (pintype "bidirectional"))
      (node (ref "P2") (pin "2") (pinfunction "2_2") (pintype "passive"))
    )
    (net (code "3") (name "/BRIGHTNESS") (class "Default")
      (node (ref "MCU1") (pin "6") (pinfunction "IO34_6") (pintype "bidirectional"))
      (node (ref "P7") (pin "2") (pinfunction "2_2") (pintype "passive"))
      (node (ref "R5") (pin "2") (pinfunction "2_2") (pintype "passive"))
    )
    (net (code "4") (name "/Boot") (class "Default")
      (node (ref "C11") (pin "1") (pinfunction "C1_1") (pintype "passive"))
      (node (ref "IC2") (pin "17") (pinfunction "BOOT_17") (pintype "passive"))
    )
    (net (code "5") (name "/CMD") (class "Default")
      (node (ref "J1") (pin "13") (pinfunction "13_13") (pintype "passive"))
      (node (ref "MCU1") (pin "19") (pinfunction "CMD_19") (pintype "bidirectional"))
    )
    (net (code "6") (name "/COLOR") (class "Default")
      (node (ref "MCU1") (pin "24") (pinfunction "IO2_24") (pintype "bidirectional"))
      (node (ref "P1") (pin "2") (pinfunction "2_2") (pintype "passive"))
      (node (ref "R1") (pin "2") (pinfunction "2_2") (pintype "passive"))
    )
    (net (code "7") (name "/Comp") (class "Default")
      (node (ref "C13") (pin "2") (pinfunction "2_2") (pintype "passive"))
      (node (ref "C14") (pin "1") (pinfunction "1_1") (pintype "passive"))
      (node (ref "IC2") (pin "8") (pinfunction "COMP_8") (pintype "passive"))
    )
    (net (code "8") (name "/DIN") (class "Default")
      (node (ref "MCU1") (pin "14") (pinfunction "IO12_14") (pintype "bidirectional"))
      (node (ref "P10") (pin "3") (pinfunction "3_3") (pintype "passive"))
    )
    (net (code "9") (name "/DMOS") (class "Default")
      (node (ref "MCU1") (pin "16") (pinfunction "IO13_16") (pintype "bidirectional"))
      (node (ref "P10") (pin "2") (pinfunction "2_2") (pintype "passive"))
    )
    (net (code "10") (name "/EN") (class "Default")
      (node (ref "MCU1") (pin "3") (pinfunction "EN_3") (pintype "input"))
      (node (ref "R3") (pin "1") (pinfunction "1_1") (pintype "passive"))
      (node (ref "S2") (pin "1") (pinfunction "1_1") (pintype "passive"))
    )
    (net (code "11") (name "/FB") (class "Default")
      (node (ref "IC2") (pin "9") (pinfunction "FB_9") (pintype "passive"))
      (node (ref "R16") (pin "1") (pinfunction "1_1") (pintype "passive"))
      (node (ref "R17") (pin "2") (pinfunction "2_2") (pintype "passive"))
    )
    (net (code "12") (name "/FREQ") (class "Default")
      (node (ref "IC2") (pin "12") (pinfunction "FREQ_12") (pintype "passive"))
      (node (ref "R20") (pin "1") (pinfunction "1_1") (pintype "passive"))
    )
    (net (code "13") (name "/I04") (class "Default")
      (node (ref "J1") (pin "16") (pinfunction "16_16") (pintype "passive"))
      (node (ref "MCU1") (pin "26") (pinfunction "IO4_26") (pintype "bidirectional"))
    )
    (net (code "14") (name "/I05") (class "Default")
      (node (ref "J1") (pin "12") (pinfunction "12_12") (pintype "passive"))
      (node (ref "MCU1") (pin "13") (pinfunction "IO14_13") (pintype "bidirectional"))
    )
    (net (code "15") (name "/I016") (class "Default")
      (node (ref "J1") (pin "8") (pinfunction "8_8") (pintype "passive"))
      (node (ref "MCU1") (pin "27") (pinfunction "IO16_27") (pintype "bidirectional"))
    )
    (net (code "16") (name "/IO0") (class "Default")
      (node (ref "MCU1") (pin "25") (pinfunction "IO0_25") (pintype "bidirectional"))
      (node (ref "R2") (pin "1") (pinfunction "1_1") (pintype "passive"))
      (node (ref "S1") (pin "2") (pinfunction "2_2") (pintype "passive"))
    )
    (net (code "17") (name "/IO26") (class "Default")
      (node (ref "J1") (pin "2") (pinfunction "2_2") (pintype "passive"))
      (node (ref "MCU1") (pin "11") (pinfunction "IO26_11") (pintype "bidirectional"))
    )
    (net (code "18") (name "/IO32") (class "Default")
      (node (ref "J1") (pin "15") (pinfunction "15_15") (pintype "passive"))
      (node (ref "MCU1") (pin "8") (pinfunction "IO32_8") (pintype "bidirectional"))
    )
    (net (code "19") (name "/Mic") (class "Default")
      (node (ref "C1") (pin "2") (pinfunction "2_2") (pintype "passive"))
      (node (ref "MCU1") (pin "30") (pinfunction "IO18_30") (pintype "bidirectional"))
    )
    (net (code "20") (name "/PATTERN") (class "Default")
      (node (ref "MCU1") (pin "10") (pinfunction "IO25_10") (pintype "bidirectional"))
      (node (ref "P5") (pin "2") (pinfunction "2_2") (pintype "passive"))
      (node (ref "R4") (pin "2") (pinfunction "2_2") (pintype "passive"))
    )
    (net (code "21") (name "/Pgood") (class "Default")
      (node (ref "C15") (pin "2") (pinfunction "2_2") (pintype "passive"))
      (node (ref "IC2") (pin "16") (pinfunction "VDD_16") (pintype "passive"))
      (node (ref "R15") (pin "1") (pinfunction "1_1") (pintype "passive"))
    )
    (net (code "22") (name "/RX") (class "Default")
      (node (ref "MCU1") (pin "34") (pinfunction "RXD0_34") (pintype "input"))
      (node (ref "P8") (pin "2") (pinfunction "2_2") (pintype "passive"))
    )
    (net (code "23") (name "/SCL") (class "Default")
      (node (ref "MCU1") (pin "36") (pinfunction "IO22_36") (pintype "bidirectional"))
      (node (ref "P6") (pin "3") (pinfunction "3_3") (pintype "passive"))
    )
    (net (code "24") (name "/SD2") (class "Default")
      (node (ref "J1") (pin "9") (pinfunction "9_9") (pintype "passive"))
      (node (ref "MCU1") (pin "17") (pinfunction "SD2_17") (pintype "bidirectional"))
    )
    (net (code "25") (name "/SD3") (class "Default")
      (node (ref "J1") (pin "11") (pinfunction "11_11") (pintype "passive"))
      (node (ref "MCU1") (pin "18") (pinfunction "SD3_18") (pintype "bidirectional"))
    )
    (net (code "26") (name "/SDA") (class "Default")
      (node (ref "MCU1") (pin "33") (pinfunction "IO21_33") (pintype "bidirectional"))
      (node (ref "P6") (pin "4") (pinfunction "4_4") (pintype "passive"))
    )
    (net (code "27") (name "/SS") (class "Default")
      (node (ref "C16") (pin "1") (pinfunction "1_1") (pintype "passive"))
      (node (ref "IC2") (pin "7") (pinfunction "SS_7") (pintype "passive"))
    )
    (net (code "28") (name "/SW") (class "Default")
      (node (ref "C11") (pin "2") (pinfunction "C2_2") (pintype "passive"))
      (node (ref "D1") (pin "1") (pinfunction "K_1") (pintype "passive"))
      (node (ref "IC2") (pin "18") (pinfunction "SW_1_18") (pintype "passive"))
      (node (ref "IC2") (pin "19") (pinfunction "SW_2_19") (pintype "passive"))
      (node (ref "IC2") (pin "20") (pinfunction "SW_3_20") (pintype "passive"))
      (node (ref "L2") (pin "1") (pinfunction "1_1") (pintype "passive"))
    )
    (net (code "29") (name "/SYNC") (class "Default")
      (node (ref "IC2") (pin "14") (pinfunction "SYNC_14") (pintype "passive"))
      (node (ref "R19") (pin "2") (pinfunction "2_2") (pintype "passive"))
    )
    (net (code "30") (name "/SensorVN") (class "Default")
      (node (ref "J1") (pin "1") (pinfunction "1_1") (pintype "passive"))
      (node (ref "MCU1") (pin "5") (pinfunction "SENSOR_VN_5") (pintype "bidirectional"))
    )
    (net (code "31") (name "/SensorVP") (class "Default")
      (node (ref "J1") (pin "3") (pinfunction "3_3") (pintype "passive"))
      (node (ref "MCU1") (pin "4") (pinfunction "SENSOR_VP_4") (pintype "bidirectional"))
    )
    (net (code "32") (name "/Standby{slash}Working") (class "Default")
      (node (ref "MCU1") (pin "31") (pinfunction "IO19_31") (pintype "bidirectional"))
      (node (ref "P4") (pin "2") (pinfunction "2_2") (pintype "passive"))
    )
    (net (code "33") (name "/Stat") (class "Default")
      (node (ref "Q1") (pin "4") (pinfunction "G2_4") (pintype "passive"))
      (node (ref "R10") (pin "2") (pinfunction "2_2") (pintype "passive"))
      (node (ref "U1") (pin "4") (pinfunction "STAT_4") (pintype "open_collector"))
    )
    (net (code "34") (name "/Studio{slash}Disco") (class "Default")
      (node (ref "MCU1") (pin "12") (pinfunction "IO27_12") (pintype "bidirectional"))
      (node (ref "P3") (pin "2") (pinfunction "2_2") (pintype "passive"))
    )
    (net (code "35") (name "/TX") (class "Default")
      (node (ref "MCU1") (pin "35") (pinfunction "TXD0_35") (pintype "output"))
      (node (ref "P8") (pin "3") (pinfunction "3_3") (pintype "passive"))
    )
    (net (code "36") (name "/Vbias") (class "Default")
      (node (ref "C12") (pin "1") (pinfunction "+_1") (pintype "passive"))
      (node (ref "FB5") (pin "1") (pinfunction "1_1") (pintype "passive"))
      (node (ref "FB6") (pin "1") (pinfunction "1_1") (pintype "passive"))
      (node (ref "IC2") (pin "15") (pinfunction "VBIAS_15") (pintype "passive"))
      (node (ref "J25") (pin "1") (pinfunction "1_1") (pintype "passive"))
      (node (ref "L2") (pin "2") (pinfunction "2_2") (pintype "passive"))
      (node (ref "R16") (pin "2") (pinfunction "2_2") (pintype "passive"))
    )
    (net (code "37") (name "3V3_out") (class "Default")
      (node (ref "FB3") (pin "2") (pinfunction "2_2") (pintype "passive"))
      (node (ref "FB4") (pin "2") (pinfunction "2_2") (pintype "passive"))
      (node (ref "J19") (pin "1") (pinfunction "1_1") (pintype "passive"))
      (node (ref "J20") (pin "2") (pinfunction "2_2") (pintype "passive"))
    )
    (net (code "38") (name "5V out") (class "Default")
      (node (ref "FB5") (pin "2") (pinfunction "2_2") (pintype "passive"))
      (node (ref "FB6") (pin "2") (pinfunction "2_2") (pintype "passive"))
      (node (ref "J27") (pin "1") (pinfunction "1_1") (pintype "passive"))
      (node (ref "J31") (pin "2") (pinfunction "2_2") (pintype "passive"))
    )
    (net (code "39") (name "6-10Vin") (class "Default")
      (node (ref "BR1") (pin "2") (pinfunction "2_2") (pintype "passive"))
      (node (ref "C10") (pin "1") (pinfunction "+_1") (pintype "passive"))
      (node (ref "C8") (pin "1") (pinfunction "1_1") (pintype "passive"))
      (node (ref "FB1") (pin "2") (pinfunction "2_2") (pintype "passive"))
      (node (ref "FB2") (pin "2") (pinfunction "2_2") (pintype "passive"))
      (node (ref "IC1") (pin "2") (pinfunction "EN_2") (pintype "passive"))
      (node (ref "IC1") (pin "3") (pinfunction "VIN_3") (pintype "passive"))
      (node (ref "IC2") (pin "1") (pinfunction "VIN_1_1") (pintype "passive"))
      (node (ref "IC2") (pin "2") (pinfunction "VIN_2_2") (pintype "passive"))
      (node (ref "IC2") (pin "3") (pinfunction "VIN_3_3") (pintype "passive"))
      (node (ref "IC2") (pin "4") (pinfunction "AVIN_4") (pintype "passive"))
      (node (ref "J14") (pin "1") (pinfunction "1_1") (pintype "passive"))
      (node (ref "J21") (pin "1") (pinfunction "1_1") (pintype "passive"))
      (node (ref "J24") (pin "1") (pinfunction "1_1") (pintype "passive"))
      (node (ref "J26") (pin "1") (pinfunction "1_1") (pintype "passive"))
      (node (ref "J30") (pin "1") (pinfunction "1_1") (pintype "passive"))
      (node (ref "R6") (pin "1") (pinfunction "1_1") (pintype "passive"))
    )
    (net (code "40") (name "GND") (class "Default")
      (node (ref "BR1") (pin "1") (pinfunction "1_1") (pintype "passive"))
      (node (ref "C10") (pin "2") (pinfunction "-_2") (pintype "passive"))
      (node (ref "C12") (pin "2") (pinfunction "-_2") (pintype "passive"))
      (node (ref "C14") (pin "2") (pinfunction "2_2") (pintype "passive"))
      (node (ref "C15") (pin "1") (pinfunction "1_1") (pintype "passive"))
      (node (ref "C16") (pin "2") (pinfunction "2_2") (pintype "passive"))
      (node (ref "C3") (pin "1") (pinfunction "1_1") (pintype "passive"))
      (node (ref "C4") (pin "1") (pinfunction "C_1") (pintype "passive"))
      (node (ref "C5") (pin "1") (pinfunction "1_1") (pintype "passive"))
      (node (ref "C8") (pin "2") (pinfunction "2_2") (pintype "passive"))
      (node (ref "C9") (pin "2") (pinfunction "2_2") (pintype "passive"))
      (node (ref "D1") (pin "2") (pinfunction "A_2") (pintype "passive"))
      (node (ref "DS1") (pin "2") (pinfunction "K_2") (pintype "passive"))
      (node (ref "IC1") (pin "1") (pinfunction "GND_1") (pintype "passive"))
      (node (ref "IC1") (pin "9") (pinfunction "EP_9") (pintype "passive"))
      (node (ref "IC2") (pin "10") (pinfunction "AGND_10") (pintype "passive"))
      (node (ref "IC2") (pin "11") (pinfunction "PGND_11") (pintype "passive"))
      (node (ref "IC2") (pin "13") (pinfunction "FPWM_13") (pintype "passive"))
      (node (ref "IC2") (pin "21") (pinfunction "GND_21") (pintype "passive"))
      (node (ref "J10") (pin "2") (pinfunction "2_2") (pintype "passive"))
      (node (ref "J13") (pin "2") (pinfunction "2_2") (pintype "passive"))
      (node (ref "J13") (pin "3") (pinfunction "3_3") (pintype "passive"))
      (node (ref "J15") (pin "2") (pinfunction "2_2") (pintype "passive"))
      (node (ref "J16") (pin "2") (pinfunction "2_2") (pintype "passive"))
      (node (ref "J20") (pin "1") (pinfunction "1_1") (pintype "passive"))
      (node (ref "J22") (pin "1") (pinfunction "1_1") (pintype "passive"))
      (node (ref "J23") (pin "1") (pinfunction "1_1") (pintype "passive"))
      (node (ref "J28") (pin "1") (pinfunction "1_1") (pintype "passive"))
      (node (ref "J29") (pin "1") (pinfunction "1_1") (pintype "passive"))
      (node (ref "J30") (pin "2") (pinfunction "2_2") (pintype "passive"))
      (node (ref "J31") (pin "1") (pinfunction "1_1") (pintype "passive"))
      (node (ref "J4") (pin "2") (pinfunction "2_2") (pintype "passive"))
      (node (ref "J4") (pin "3") (pinfunction "3_3") (pintype "passive"))
      (node (ref "J5") (pin "1") (pinfunction "1_1") (pintype "passive"))
      (node (ref "J6") (pin "1") (pinfunction "1_1") (pintype "passive"))
      (node (ref "J7") (pin "1") (pinfunction "1_1") (pintype "passive"))
      (node (ref "J8") (pin "1") (pinfunction "1_1") (pintype "passive"))
      (node (ref "J9") (pin "1") (pinfunction "1_1") (pintype "passive"))
      (node (ref "MCU1") (pin "1") (pinfunction "GND_1") (pintype "power_in"))
      (node (ref "MCU1") (pin "15") (pinfunction "GND_15") (pintype "power_in"))
      (node (ref "MCU1") (pin "38") (pinfunction "GND_38") (pintype "power_in"))
      (node (ref "MCU1") (pin "39") (pinfunction "GND_39") (pintype "power_in"))
      (node (ref "P2") (pin "1") (pinfunction "1_1") (pintype "passive"))
      (node (ref "P3") (pin "1") (pinfunction "1_1") (pintype "passive"))
      (node (ref "P4") (pin "1") (pinfunction "1_1") (pintype "passive"))
      (node (ref "P6") (pin "1") (pinfunction "1_1") (pintype "passive"))
      (node (ref "P8") (pin "1") (pinfunction "1_1") (pintype "passive"))
      (node (ref "P9") (pin "3") (pinfunction "3_3") (pintype "passive"))
      (node (ref "Q2") (pin "1") (pinfunction "E_1") (pintype "passive"))
      (node (ref "R1") (pin "1") (pinfunction "1_1") (pintype "passive"))
      (node (ref "R13") (pin "1") (pinfunction "1_1") (pintype "passive"))
      (node (ref "R14") (pin "1") (pinfunction "1_1") (pintype "passive"))
      (node (ref "R17") (pin "1") (pinfunction "1_1") (pintype "passive"))
      (node (ref "R18") (pin "1") (pinfunction "1_1") (pintype "passive"))
      (node (ref "R19") (pin "1") (pinfunction "1_1") (pintype "passive"))
      (node (ref "R20") (pin "2") (pinfunction "2_2") (pintype "passive"))
      (node (ref "R4") (pin "1") (pinfunction "1_1") (pintype "passive"))
      (node (ref "R5") (pin "1") (pinfunction "1_1") (pintype "passive"))
      (node (ref "S1") (pin "1") (pinfunction "1_1") (pintype "passive"))
      (node (ref "S2") (pin "2") (pinfunction "2_2") (pintype "passive"))
      (node (ref "U1") (pin "2") (pinfunction "GND_2") (pintype "power_in"))
    )
    (net (code "41") (name "Net-(C2-Pad1)") (class "Default")
      (node (ref "C2") (pin "1") (pinfunction "1_1") (pintype "passive"))
      (node (ref "P9") (pin "2") (pinfunction "2_2") (pintype "passive"))
      (node (ref "R8") (pin "1") (pinfunction "1_1") (pintype "passive"))
    )
    (net (code "42") (name "Net-(C3-Pad2)") (class "Default")
      (node (ref "C3") (pin "2") (pinfunction "2_2") (pintype "passive"))
      (node (ref "J10") (pin "1") (pinfunction "1_1") (pintype "passive"))
      (node (ref "J3") (pin "1") (pinfunction "1_1") (pintype "passive"))
      (node (ref "Q1") (pin "5") (pinfunction "D2_5") (pintype "passive"))
      (node (ref "Q1") (pin "6") (pinfunction "D2_6") (pintype "passive"))
    )
    (net (code "43") (name "Net-(C4-A)") (class "Default")
      (node (ref "C4") (pin "2") (pinfunction "A_2") (pintype "passive"))
      (node (ref "FB1") (pin "1") (pinfunction "1_1") (pintype "passive"))
      (node (ref "FB2") (pin "1") (pinfunction "1_1") (pintype "passive"))
      (node (ref "J11") (pin "1") (pinfunction "1_1") (pintype "passive"))
      (node (ref "Q1") (pin "1") (pinfunction "S1_1") (pintype "passive"))
      (node (ref "Q1") (pin "3") (pinfunction "S2_3") (pintype "passive"))
      (node (ref "R10") (pin "1") (pinfunction "1_1") (pintype "passive"))
      (node (ref "U1") (pin "6") (pinfunction "SENSE_6") (pintype "passive"))
    )
    (net (code "44") (name "Net-(C5-Pad2)") (class "Default")
      (node (ref "C5") (pin "2") (pinfunction "2_2") (pintype "passive"))
      (node (ref "J12") (pin "2") (pinfunction "2_2") (pintype "passive"))
      (node (ref "J13") (pin "1") (pinfunction "1_1") (pintype "passive"))
      (node (ref "J16") (pin "1") (pinfunction "1_1") (pintype "passive"))
      (node (ref "J17") (pin "1") (pinfunction "1_1") (pintype "passive"))
    )
    (net (code "45") (name "Net-(C7-Pad2)") (class "Default")
      (node (ref "C7") (pin "2") (pinfunction "2_2") (pintype "passive"))
      (node (ref "C9") (pin "1") (pinfunction "1_1") (pintype "passive"))
      (node (ref "FB3") (pin "1") (pinfunction "1_1") (pintype "passive"))
      (node (ref "FB4") (pin "1") (pinfunction "1_1") (pintype "passive"))
      (node (ref "J18") (pin "1") (pinfunction "1_1") (pintype "passive"))
      (node (ref "L1") (pin "2") (pinfunction "2_2") (pintype "passive"))
      (node (ref "R11") (pin "2") (pinfunction "2_2") (pintype "passive"))
      (node (ref "R12") (pin "2") (pinfunction "2_2") (pintype "passive"))
    )
    (net (code "46") (name "Net-(C13-Pad1)") (class "Default")
      (node (ref "C13") (pin "1") (pinfunction "1_1") (pintype "passive"))
      (node (ref "R18") (pin "2") (pinfunction "2_2") (pintype "passive"))
    )
    (net (code "47") (name "Net-(DS1-A)") (class "Default")
      (node (ref "DS1") (pin "1") (pinfunction "A_1") (pintype "passive"))
      (node (ref "R6") (pin "2") (pinfunction "2_2") (pintype "passive"))
    )
    (net (code "48") (name "Net-(IC1-BOOT)") (class "Default")
      (node (ref "C6") (pin "1") (pinfunction "1_1") (pintype "passive"))
      (node (ref "IC1") (pin "7") (pinfunction "BOOT_7") (pintype "passive"))
    )
    (net (code "49") (name "Net-(IC1-FB)") (class "Default")
      (node (ref "C7") (pin "1") (pinfunction "1_1") (pintype "passive"))
      (node (ref "IC1") (pin "5") (pinfunction "FB_5") (pintype "passive"))
      (node (ref "R12") (pin "1") (pinfunction "1_1") (pintype "passive"))
      (node (ref "R14") (pin "2") (pinfunction "2_2") (pintype "passive"))
    )
    (net (code "50") (name "Net-(IC1-PG)") (class "Default")
      (node (ref "IC1") (pin "6") (pinfunction "PG_6") (pintype "passive"))
      (node (ref "R11") (pin "1") (pinfunction "1_1") (pintype "passive"))
    )
    (net (code "51") (name "Net-(IC1-RT{slash}SYNC)") (class "Default")
      (node (ref "IC1") (pin "4") (pinfunction "RT/SYNC_4") (pintype "passive"))
      (node (ref "R13") (pin "2") (pinfunction "2_2") (pintype "passive"))
    )
    (net (code "52") (name "Net-(IC1-SW)") (class "Default")
      (node (ref "C6") (pin "2") (pinfunction "2_2") (pintype "passive"))
      (node (ref "IC1") (pin "8") (pinfunction "SW_8") (pintype "passive"))
      (node (ref "L1") (pin "1") (pinfunction "1_1") (pintype "passive"))
    )
    (net (code "53") (name "Net-(IC2-PGOOD)") (class "Default")
      (node (ref "IC2") (pin "5") (pinfunction "PGOOD_5") (pintype "passive"))
      (node (ref "R15") (pin "2") (pinfunction "2_2") (pintype "passive"))
    )
    (net (code "54") (name "Net-(J2-Pad1)") (class "Default")
      (node (ref "J2") (pin "1") (pinfunction "1_1") (pintype "passive"))
      (node (ref "J3") (pin "2") (pinfunction "2_2") (pintype "passive"))
      (node (ref "J4") (pin "1") (pinfunction "1_1") (pintype "passive"))
    )
    (net (code "55") (name "Net-(Q1A-G1)") (class "Default")
      (node (ref "Q1") (pin "2") (pinfunction "G1_2") (pintype "passive"))
      (node (ref "U1") (pin "5") (pinfunction "GATE_5") (pintype "passive"))
    )
    (net (code "56") (name "Net-(Q2-B)") (class "Default")
      (node (ref "C2") (pin "2") (pinfunction "2_2") (pintype "passive"))
      (node (ref "Q2") (pin "2") (pinfunction "B_2") (pintype "passive"))
      (node (ref "R9") (pin "1") (pinfunction "1_1") (pintype "passive"))
    )
    (net (code "57") (name "Net-(Q2-C)") (class "Default")
      (node (ref "C1") (pin "1") (pinfunction "1_1") (pintype "passive"))
      (node (ref "Q2") (pin "3") (pinfunction "C_3") (pintype "passive"))
      (node (ref "R7") (pin "1") (pinfunction "1_1") (pintype "passive"))
      (node (ref "R9") (pin "2") (pinfunction "2_2") (pintype "passive"))
    )
    (net (code "58") (name "Net-(U1-CTL)") (class "Default")
      (node (ref "J15") (pin "1") (pinfunction "1_1") (pintype "passive"))
      (node (ref "U1") (pin "3") (pinfunction "CTL_3") (pintype "input"))
    )
    (net (code "59") (name "Net-(U1-VIN)") (class "Default")
      (node (ref "J12") (pin "1") (pinfunction "1_1") (pintype "passive"))
      (node (ref "Q1") (pin "7") (pinfunction "D1_7") (pintype "passive"))
      (node (ref "Q1") (pin "8") (pinfunction "D1_8") (pintype "passive"))
      (node (ref "U1") (pin "1") (pinfunction "VIN_1") (pintype "power_in"))
    )
    (net (code "60") (name "unconnected-(IC2-EN-Pad6)") (class "Default")
      (node (ref "IC2") (pin "6") (pinfunction "EN_6") (pintype "passive+no_connect"))
    )
    (net (code "61") (name "unconnected-(J1-Pad4)") (class "Default")
      (node (ref "J1") (pin "4") (pinfunction "4_4") (pintype "passive"))
    )
    (net (code "62") (name "unconnected-(J1-Pad5)") (class "Default")
      (node (ref "J1") (pin "5") (pinfunction "5_5") (pintype "passive"))
    )
    (net (code "63") (name "unconnected-(J1-Pad6)") (class "Default")
      (node (ref "J1") (pin "6") (pinfunction "6_6") (pintype "passive"))
    )
    (net (code "64") (name "unconnected-(J1-Pad7)") (class "Default")
      (node (ref "J1") (pin "7") (pinfunction "7_7") (pintype "passive"))
    )
    (net (code "65") (name "unconnected-(J1-Pad10)") (class "Default")
      (node (ref "J1") (pin "10") (pinfunction "10_10") (pintype "passive"))
    )
    (net (code "66") (name "unconnected-(J1-Pad14)") (class "Default")
      (node (ref "J1") (pin "14") (pinfunction "14_14") (pintype "passive"))
    )
    (net (code "67") (name "unconnected-(MCU1-CLK-Pad20)") (class "Default")
      (node (ref "MCU1") (pin "20") (pinfunction "CLK_20") (pintype "input+no_connect"))
    )
    (net (code "68") (name "unconnected-(MCU1-IO5-Pad29)") (class "Default")
      (node (ref "MCU1") (pin "29") (pinfunction "IO5_29") (pintype "bidirectional"))
    )
    (net (code "69") (name "unconnected-(MCU1-IO15-Pad23)") (class "Default")
      (node (ref "MCU1") (pin "23") (pinfunction "IO15_23") (pintype "bidirectional"))
    )
    (net (code "70") (name "unconnected-(MCU1-IO17-Pad28)") (class "Default")
      (node (ref "MCU1") (pin "28") (pinfunction "IO17_28") (pintype "bidirectional"))
    )
    (net (code "71") (name "unconnected-(MCU1-IO23-Pad37)") (class "Default")
      (node (ref "MCU1") (pin "37") (pinfunction "IO23_37") (pintype "bidirectional"))
    )
    (net (code "72") (name "unconnected-(MCU1-IO35-Pad7)") (class "Default")
      (node (ref "MCU1") (pin "7") (pinfunction "IO35_7") (pintype "bidirectional+no_connect"))
    )
    (net (code "73") (name "unconnected-(MCU1-NC-Pad32)") (class "Default")
      (node (ref "MCU1") (pin "32") (pinfunction "NC_32") (pintype "passive+no_connect"))
    )
    (net (code "74") (name "unconnected-(MCU1-SD0-Pad21)") (class "Default")
      (node (ref "MCU1") (pin "21") (pinfunction "SD0_21") (pintype "bidirectional"))
    )
    (net (code "75") (name "unconnected-(MCU1-SD1-Pad22)") (class "Default")
      (node (ref "MCU1") (pin "22") (pinfunction "SD1_22") (pintype "bidirectional"))
    )
    (net (code "76") (name "unconnected-(P1-Pad1)") (class "Default")
      (node (ref "P1") (pin "1") (pinfunction "1_1") (pintype "passive"))
    )
    (net (code "77") (name "unconnected-(P5-Pad1)") (class "Default")
      (node (ref "P5") (pin "1") (pinfunction "1_1") (pintype "passive"))
    )
    (net (code "78") (name "unconnected-(P7-Pad1)") (class "Default")
      (node (ref "P7") (pin "1") (pinfunction "1_1") (pintype "passive"))
    )
    (net (code "79") (name "unconnected-(P9-Pad1)") (class "Default")
      (node (ref "P9") (pin "1") (pinfunction "1_1") (pintype "passive"))
    )
    (net (code "80") (name "unconnected-(P10-Pad1)") (class "Default")
      (node (ref "P10") (pin "1") (pinfunction "1_1") (pintype "passive"))
    )
  )
)
